# connectors.net
KiCad netlist of a schematic drawn in Altium Designer
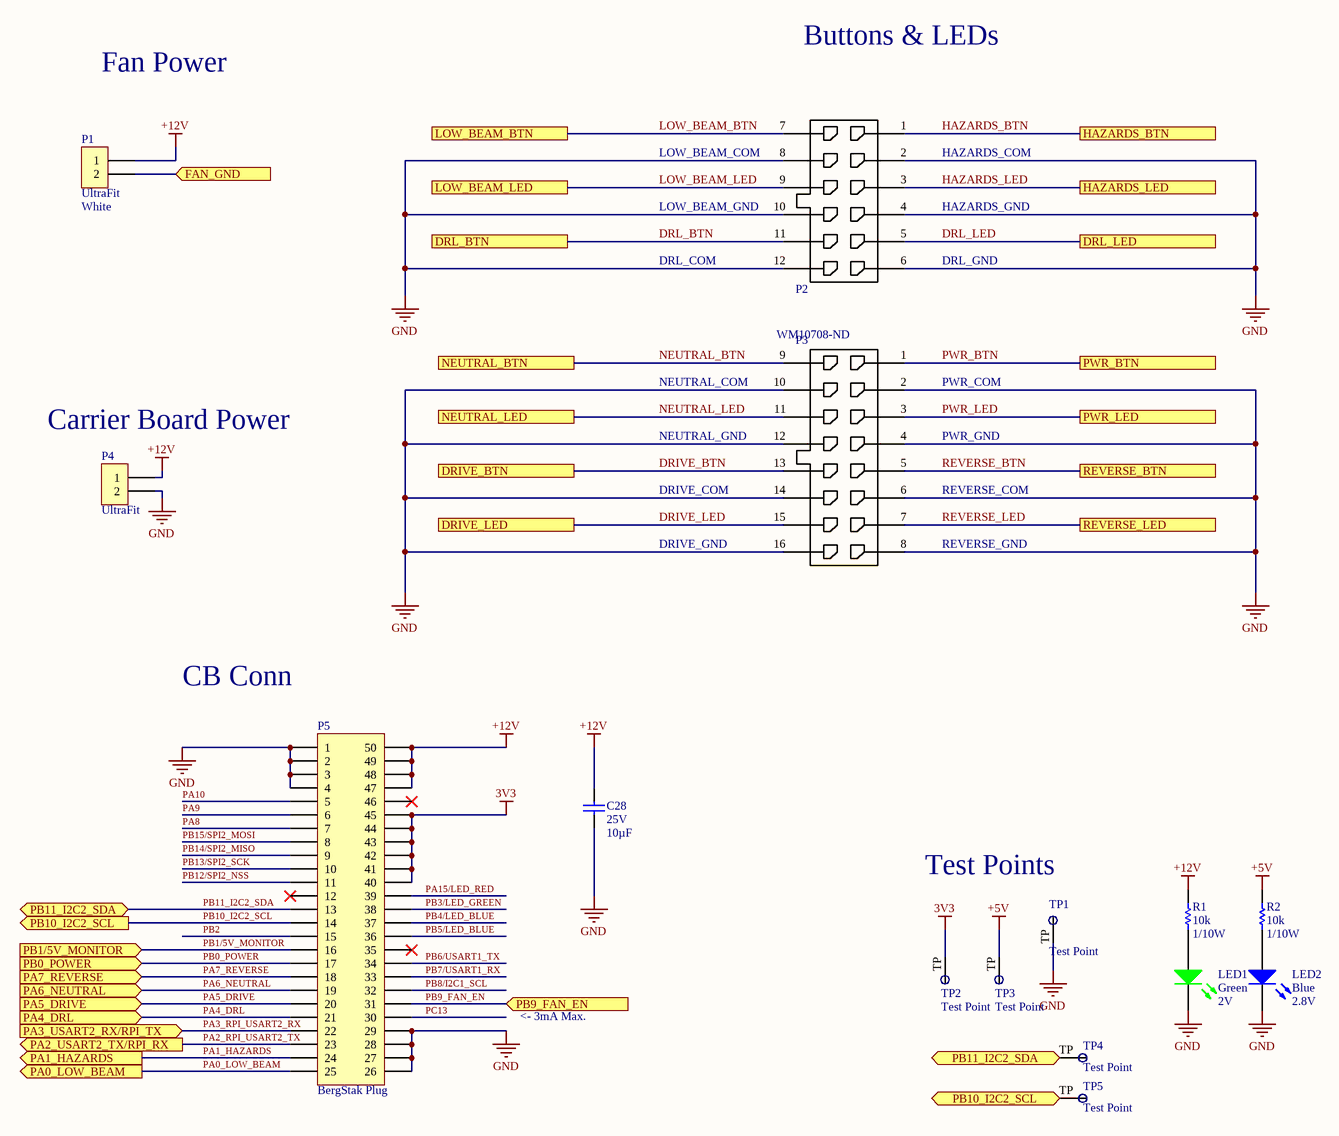
[diagram p0: connectors.SchDoc]

(export (version "E")
  (design (tool "Eeschema 10.0.6"))
  (components
    (comp (ref "C28")
      (value "CAP CER 10uF 25V 10% X5R 0805")
      (footprint "CAP, 0805")
      (description "10µF ±10% 25V Ceramic Capacitor X5R 0805 (2012 Metric)")
      (fields
        (field (name "MANUFACTURER") "Murata Electronics North America")
        (field (name "MANUFACTURER PART NUMBER") "GRM21BR61E106KA73L")
        (field (name "VOLTAGE - RATED") "25V")
        (field (name "CAPACITANCE") "10µF")
      )
      (libsource (lib "altium-import") (part "root_0_CAP CER 10uF 25V 10% X5R 0805_"))
    )
    (comp (ref "LED1")
      (value "LED GREEN CLEAR 2V 0603")
      (footprint "LED_0603")
      (description "Green 572nm LED Indication - Discrete 2V 0603 (1608 Metric)")
      (fields
        (field (name "MANUFACTURER") "Wurth Electronics Inc.")
        (field (name "MANUFACTURER PART NUMBER") "150060VS75000")
        (field (name "COLOR") "Green")
        (field (name "VOLTAGE - FORWARD (VF) (TYP)") "2V")
      )
      (libsource (lib "Schematic Diagrams") (part "LED GREEN CLEAR 2V 0603"))
    )
    (comp (ref "LED2")
      (value "LED BLUE CLEAR 2.8V 0603")
      (footprint "LED_0603")
      (description "Blue 470nm LED Indication - Discrete 2.8V 0603 (1608 Metric)")
      (fields (field (name "COLOR") "Blue") (field (name "VOLTAGE - FORWARD (VF) (TYP)") "2.8V"))
      (libsource (lib "Schematic Diagrams") (part "LED BLUE CLEAR 2.8V 0603"))
    )
    (comp (ref "P1")
      (value "CONN 2POS ULTRA-FIT NATURAL COLOR 0.138\"")
      (footprint "CONN, 2POS ULTRA-FIT - NATURAL COLOR")
      (description "2 Positions Header, Shrouded Connector 0.138\" (3.50mm) Through Hole")
      (fields
        (field (name "VOLTAGE") "400V")
        (field (name "SERIES") "UltraFit")
        (field (name "COLOR") "White")
      )
      (libsource (lib "Schematic Diagrams") (part "CONN 2POS ULTRA-FIT NATURAL COLOR 0.138{dblquote}"))
    )
    (comp (ref "P2")
      (value "CONN 12POS MICRO-FIT 3mm")
      (footprint "CONN, 12POS MICRO-FIT 3mm")
      (description "Connector Header Through Hole 12 position 0.118\" (3.00mm)")
      (fields
        (field (name "MANUFACTURER") "Molex, LLC")
        (field (name "MANUFACTURER PART NUMBER") "0430451227")
      )
      (libsource (lib "Schematic Diagrams") (part "CONN 12POS MICRO-FIT 3mm"))
    )
    (comp (ref "P3")
      (value "CONN 16POS MICRO-FIT 3mm")
      (footprint "Footprints:CONN, 16POS MICRO-FIT 3MM")
      (description "Connector Header Through Hole 16 position 0.118\"(3.00mm)")
      (fields
        (field (name "MANUFACTURER") "Molex")
        (field (name "MANUFACTURER PART NUMBER") "0430451627")
        (field (name "SUPPLIER PART NUMBER 1") "WM10708-ND")
      )
      (libsource (lib "Schematic Diagrams") (part "CONN 16POS MICRO-FIT 3mm"))
    )
    (comp (ref "P4")
      (value "CONN 2POS ULTRA-FIT 0.138\"")
      (footprint "CONN, 2POS ULTRA-FIT")
      (description "2 Positions Header, Shrouded Connector 0.138\" (3.50mm) Through Hole Gold")
      (fields (field (name "VOLTAGE") "400V") (field (name "SERIES") "UltraFit"))
      (libsource (lib "Schematic Diagrams") (part "CONN 2POS ULTRA-FIT 0.138{dblquote}"))
    )
    (comp (ref "P5")
      (value "CONN 50POS Bergstak Plug 0.02\"")
      (footprint "CONN, Bergstak 50 Pos Plug")
      (description "50 Position Connector Plug, Outer Shroud Contacts Surface Mount Gold")
      (fields (field (name "SERIES") "BergStak Plug"))
      (libsource (lib "Schematic Diagrams") (part "CONN 50POS Bergstak Plug 0.02{dblquote}"))
    )
    (comp (ref "R1")
      (value "RES 10K OHM 1% 1/10W 0603")
      (footprint "RES, 0603")
      (description "RES SMD 10K OHM 1% 1/10W 0603")
      (fields
        (field (name "TOLERANCE") "±1%")
        (field (name "RESISTANCE") "10k")
        (field (name "POWER") "1/10W")
      )
      (libsource (lib "Schematic Diagrams") (part "RES 10K OHM 1% 1/10W 0603"))
    )
    (comp (ref "R2")
      (value "RES 10K OHM 1% 1/10W 0603")
      (footprint "RES, 0603")
      (description "RES SMD 10K OHM 1% 1/10W 0603")
      (fields
        (field (name "TOLERANCE") "±1%")
        (field (name "RESISTANCE") "10k")
        (field (name "POWER") "1/10W")
      )
      (libsource (lib "Schematic Diagrams") (part "RES 10K OHM 1% 1/10W 0603"))
    )
    (comp (ref "TP1")
      (value "Test Point")
      (footprint "Test Point")
      (libsource (lib "Schematic Diagrams") (part "Test Point"))
    )
    (comp (ref "TP2")
      (value "Test Point")
      (footprint "Test Point")
      (libsource (lib "Schematic Diagrams") (part "Test Point"))
    )
    (comp (ref "TP3")
      (value "Test Point")
      (footprint "Test Point")
      (libsource (lib "Schematic Diagrams") (part "Test Point"))
    )
    (comp (ref "TP4")
      (value "Test Point")
      (footprint "Test Point")
      (libsource (lib "Schematic Diagrams") (part "Test Point"))
    )
    (comp (ref "TP5")
      (value "Test Point")
      (footprint "Test Point")
      (libsource (lib "Schematic Diagrams") (part "Test Point"))
    )
  )
  (nets
    (net (code "1") (name "+5V") (class "Default")
      (node (ref "R2") (pin "1") (pinfunction "1_1") (pintype "passive"))
      (node (ref "TP3") (pin "TP") (pinfunction "1_TP") (pintype "passive"))
    )
    (net (code "2") (name "+12V") (class "Default")
      (node (ref "C28") (pin "1") (pinfunction "1_1") (pintype "passive"))
      (node (ref "P1") (pin "1") (pinfunction "1_1") (pintype "passive"))
      (node (ref "P4") (pin "1") (pinfunction "1_1") (pintype "passive"))
      (node (ref "P5") (pin "47") (pinfunction "47_47") (pintype "passive"))
      (node (ref "P5") (pin "48") (pinfunction "48_48") (pintype "passive"))
      (node (ref "P5") (pin "49") (pinfunction "49_49") (pintype "passive"))
      (node (ref "P5") (pin "50") (pinfunction "50_50") (pintype "passive"))
      (node (ref "R1") (pin "1") (pinfunction "1_1") (pintype "passive"))
    )
    (net (code "3") (name "/DRIVE_BTN") (class "Default")
      (node (ref "P3") (pin "13") (pinfunction "13_13") (pintype "passive"))
    )
    (net (code "4") (name "/DRIVE_LED") (class "Default")
      (node (ref "P3") (pin "15") (pinfunction "15_15") (pintype "passive"))
    )
    (net (code "5") (name "/DRL_BTN") (class "Default")
      (node (ref "P2") (pin "11") (pinfunction "11_11") (pintype "passive"))
    )
    (net (code "6") (name "/DRL_LED") (class "Default")
      (node (ref "P2") (pin "5") (pinfunction "5_5") (pintype "passive"))
    )
    (net (code "7") (name "/FAN_GND") (class "Default")
      (node (ref "P1") (pin "2") (pinfunction "2_2") (pintype "passive"))
    )
    (net (code "8") (name "/HAZARDS_BTN") (class "Default")
      (node (ref "P2") (pin "1") (pinfunction "1_1") (pintype "passive"))
    )
    (net (code "9") (name "/HAZARDS_LED") (class "Default")
      (node (ref "P2") (pin "3") (pinfunction "3_3") (pintype "passive"))
    )
    (net (code "10") (name "/LOW_BEAM_BTN") (class "Default")
      (node (ref "P2") (pin "7") (pinfunction "7_7") (pintype "passive"))
    )
    (net (code "11") (name "/LOW_BEAM_LED") (class "Default")
      (node (ref "P2") (pin "9") (pinfunction "9_9") (pintype "passive"))
    )
    (net (code "12") (name "/NEUTRAL_BTN") (class "Default")
      (node (ref "P3") (pin "9") (pinfunction "9_9") (pintype "passive"))
    )
    (net (code "13") (name "/NEUTRAL_LED") (class "Default")
      (node (ref "P3") (pin "11") (pinfunction "11_11") (pintype "passive"))
    )
    (net (code "14") (name "/PA0_LOW_BEAM") (class "Default")
      (node (ref "P5") (pin "25") (pinfunction "25_25") (pintype "passive"))
    )
    (net (code "15") (name "/PA1_HAZARDS") (class "Default")
      (node (ref "P5") (pin "24") (pinfunction "24_24") (pintype "passive"))
    )
    (net (code "16") (name "/PA2_RPI_USART2_TX") (class "Default")
      (node (ref "P5") (pin "23") (pinfunction "23_23") (pintype "passive"))
    )
    (net (code "17") (name "/PA3_RPI_USART2_RX") (class "Default")
      (node (ref "P5") (pin "22") (pinfunction "22_22") (pintype "passive"))
    )
    (net (code "18") (name "/PA4_DRL") (class "Default")
      (node (ref "P5") (pin "21") (pinfunction "21_21") (pintype "passive"))
    )
    (net (code "19") (name "/PA5_DRIVE") (class "Default")
      (node (ref "P5") (pin "20") (pinfunction "20_20") (pintype "passive"))
    )
    (net (code "20") (name "/PA6_NEUTRAL") (class "Default")
      (node (ref "P5") (pin "19") (pinfunction "19_19") (pintype "passive"))
    )
    (net (code "21") (name "/PA7_REVERSE") (class "Default")
      (node (ref "P5") (pin "18") (pinfunction "18_18") (pintype "passive"))
    )
    (net (code "22") (name "/PA8") (class "Default")
      (node (ref "P5") (pin "7") (pinfunction "7_7") (pintype "passive"))
    )
    (net (code "23") (name "/PA9") (class "Default")
      (node (ref "P5") (pin "6") (pinfunction "6_6") (pintype "passive"))
    )
    (net (code "24") (name "/PA10") (class "Default")
      (node (ref "P5") (pin "5") (pinfunction "5_5") (pintype "passive"))
    )
    (net (code "25") (name "/PA15{slash}LED_RED") (class "Default")
      (node (ref "P5") (pin "39") (pinfunction "39_39") (pintype "passive"))
    )
    (net (code "26") (name "/PB0_POWER") (class "Default")
      (node (ref "P5") (pin "17") (pinfunction "17_17") (pintype "passive"))
    )
    (net (code "27") (name "/PB1{slash}5V_MONITOR") (class "Default")
      (node (ref "P5") (pin "16") (pinfunction "16_16") (pintype "passive"))
    )
    (net (code "28") (name "/PB2") (class "Default")
      (node (ref "P5") (pin "15") (pinfunction "15_15") (pintype "passive"))
    )
    (net (code "29") (name "/PB3{slash}LED_GREEN") (class "Default")
      (node (ref "P5") (pin "38") (pinfunction "38_38") (pintype "passive"))
    )
    (net (code "30") (name "/PB4{slash}LED_BLUE") (class "Default")
      (node (ref "P5") (pin "37") (pinfunction "37_37") (pintype "passive"))
    )
    (net (code "31") (name "/PB5{slash}LED_BLUE") (class "Default")
      (node (ref "P5") (pin "36") (pinfunction "36_36") (pintype "passive"))
    )
    (net (code "32") (name "/PB6{slash}USART1_TX") (class "Default")
      (node (ref "P5") (pin "34") (pinfunction "34_34") (pintype "passive"))
    )
    (net (code "33") (name "/PB7{slash}USART1_RX") (class "Default")
      (node (ref "P5") (pin "33") (pinfunction "33_33") (pintype "passive"))
    )
    (net (code "34") (name "/PB8{slash}I2C1_SCL") (class "Default")
      (node (ref "P5") (pin "32") (pinfunction "32_32") (pintype "passive"))
    )
    (net (code "35") (name "/PB9_FAN_EN") (class "Default")
      (node (ref "P5") (pin "31") (pinfunction "31_31") (pintype "passive"))
    )
    (net (code "36") (name "/PB10_I2C2_SCL") (class "Default")
      (node (ref "P5") (pin "14") (pinfunction "14_14") (pintype "passive"))
      (node (ref "TP5") (pin "TP") (pinfunction "1_TP") (pintype "passive"))
    )
    (net (code "37") (name "/PB11_I2C2_SDA") (class "Default")
      (node (ref "P5") (pin "13") (pinfunction "13_13") (pintype "passive"))
      (node (ref "TP4") (pin "TP") (pinfunction "1_TP") (pintype "passive"))
    )
    (net (code "38") (name "/PB12{slash}SPI2_NSS") (class "Default")
      (node (ref "P5") (pin "11") (pinfunction "11_11") (pintype "passive"))
    )
    (net (code "39") (name "/PB13{slash}SPI2_SCK") (class "Default")
      (node (ref "P5") (pin "10") (pinfunction "10_10") (pintype "passive"))
    )
    (net (code "40") (name "/PB14{slash}SPI2_MISO") (class "Default")
      (node (ref "P5") (pin "9") (pinfunction "9_9") (pintype "passive"))
    )
    (net (code "41") (name "/PB15{slash}SPI2_MOSI") (class "Default")
      (node (ref "P5") (pin "8") (pinfunction "8_8") (pintype "passive"))
    )
    (net (code "42") (name "/PC13") (class "Default")
      (node (ref "P5") (pin "30") (pinfunction "30_30") (pintype "passive"))
    )
    (net (code "43") (name "/PWR_BTN") (class "Default")
      (node (ref "P3") (pin "1") (pinfunction "1_1") (pintype "passive"))
    )
    (net (code "44") (name "/PWR_LED") (class "Default")
      (node (ref "P3") (pin "3") (pinfunction "3_3") (pintype "passive"))
    )
    (net (code "45") (name "/REVERSE_BTN") (class "Default")
      (node (ref "P3") (pin "5") (pinfunction "5_5") (pintype "passive"))
    )
    (net (code "46") (name "/REVERSE_LED") (class "Default")
      (node (ref "P3") (pin "7") (pinfunction "7_7") (pintype "passive"))
    )
    (net (code "47") (name "3V3") (class "Default")
      (node (ref "P5") (pin "40") (pinfunction "40_40") (pintype "passive"))
      (node (ref "P5") (pin "41") (pinfunction "41_41") (pintype "passive"))
      (node (ref "P5") (pin "42") (pinfunction "42_42") (pintype "passive"))
      (node (ref "P5") (pin "43") (pinfunction "43_43") (pintype "passive"))
      (node (ref "P5") (pin "44") (pinfunction "44_44") (pintype "passive"))
      (node (ref "P5") (pin "45") (pinfunction "45_45") (pintype "passive"))
      (node (ref "TP2") (pin "TP") (pinfunction "1_TP") (pintype "passive"))
    )
    (net (code "48") (name "GND") (class "Default")
      (node (ref "C28") (pin "2") (pinfunction "2_2") (pintype "passive"))
      (node (ref "LED1") (pin "2") (pinfunction "K_2") (pintype "passive"))
      (node (ref "LED2") (pin "2") (pinfunction "K_2") (pintype "passive"))
      (node (ref "P2") (pin "10") (pinfunction "10_10") (pintype "passive"))
      (node (ref "P2") (pin "12") (pinfunction "12_12") (pintype "passive"))
      (node (ref "P2") (pin "2") (pinfunction "2_2") (pintype "passive"))
      (node (ref "P2") (pin "4") (pinfunction "4_4") (pintype "passive"))
      (node (ref "P2") (pin "6") (pinfunction "6_6") (pintype "passive"))
      (node (ref "P2") (pin "8") (pinfunction "8_8") (pintype "passive"))
      (node (ref "P3") (pin "10") (pinfunction "10_10") (pintype "passive"))
      (node (ref "P3") (pin "12") (pinfunction "12_12") (pintype "passive"))
      (node (ref "P3") (pin "14") (pinfunction "14_14") (pintype "passive"))
      (node (ref "P3") (pin "16") (pinfunction "16_16") (pintype "passive"))
      (node (ref "P3") (pin "2") (pinfunction "2_2") (pintype "passive"))
      (node (ref "P3") (pin "4") (pinfunction "4_4") (pintype "passive"))
      (node (ref "P3") (pin "6") (pinfunction "6_6") (pintype "passive"))
      (node (ref "P3") (pin "8") (pinfunction "8_8") (pintype "passive"))
      (node (ref "P4") (pin "2") (pinfunction "2_2") (pintype "passive"))
      (node (ref "P5") (pin "1") (pinfunction "1_1") (pintype "passive"))
      (node (ref "P5") (pin "2") (pinfunction "2_2") (pintype "passive"))
      (node (ref "P5") (pin "26") (pinfunction "26_26") (pintype "passive"))
      (node (ref "P5") (pin "27") (pinfunction "27_27") (pintype "passive"))
      (node (ref "P5") (pin "28") (pinfunction "28_28") (pintype "passive"))
      (node (ref "P5") (pin "29") (pinfunction "29_29") (pintype "passive"))
      (node (ref "P5") (pin "3") (pinfunction "3_3") (pintype "passive"))
      (node (ref "P5") (pin "4") (pinfunction "4_4") (pintype "passive"))
      (node (ref "TP1") (pin "TP") (pinfunction "1_TP") (pintype "passive"))
    )
    (net (code "49") (name "Net-(LED1-A)") (class "Default")
      (node (ref "LED1") (pin "1") (pinfunction "A_1") (pintype "passive"))
      (node (ref "R1") (pin "2") (pinfunction "2_2") (pintype "passive"))
    )
    (net (code "50") (name "Net-(LED2-A)") (class "Default")
      (node (ref "LED2") (pin "1") (pinfunction "A_1") (pintype "passive"))
      (node (ref "R2") (pin "2") (pinfunction "2_2") (pintype "passive"))
    )
    (net (code "51") (name "unconnected-(P5-Pad12)") (class "Default")
      (node (ref "P5") (pin "12") (pinfunction "12_12") (pintype "passive+no_connect"))
    )
    (net (code "52") (name "unconnected-(P5-Pad35)") (class "Default")
      (node (ref "P5") (pin "35") (pinfunction "35_35") (pintype "passive+no_connect"))
    )
    (net (code "53") (name "unconnected-(P5-Pad46)") (class "Default")
      (node (ref "P5") (pin "46") (pinfunction "46_46") (pintype "passive+no_connect"))
    )
  )
)
